# Supply.net
KiCad netlist of a schematic drawn in Altium Designer
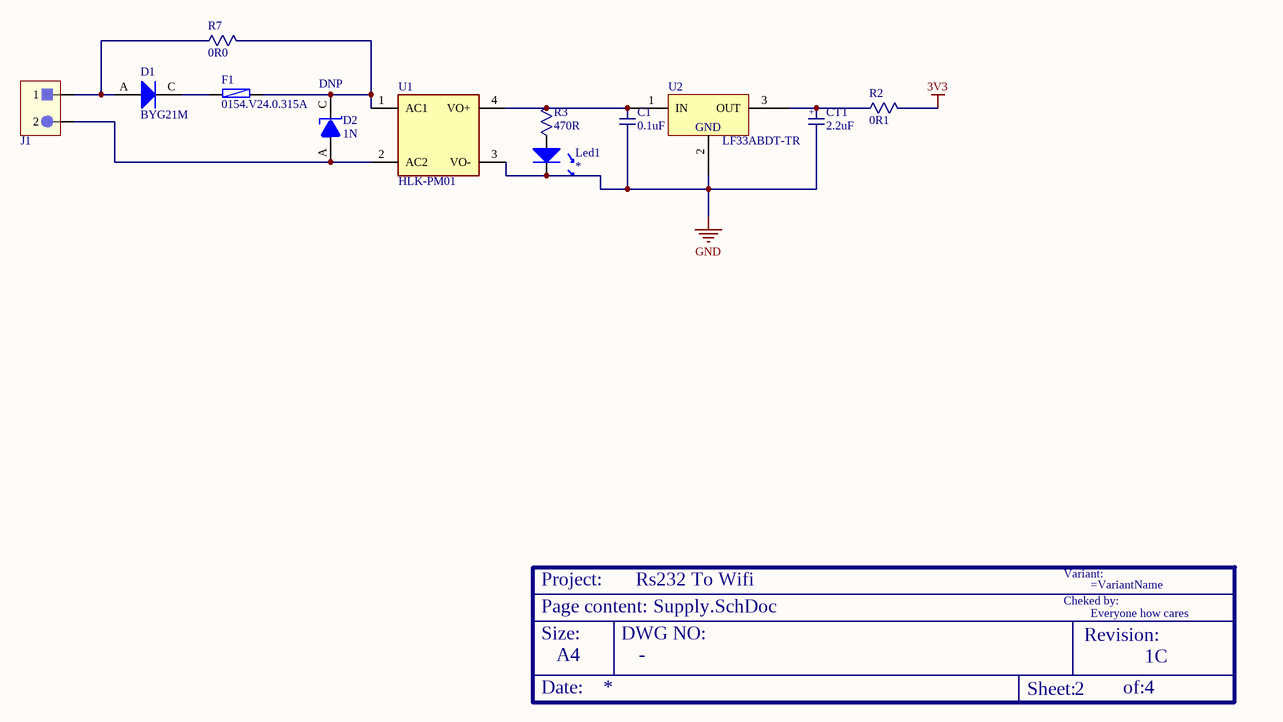
[diagram p0: Supply.SchDoc]

(export (version "E")
  (design (tool "Eeschema 10.0.6"))
  (components
    (comp (ref "C1")
      (value "0.1uF")
      (footprint "0603C")
      (description "Ceramic Capacitor")
      (libsource (lib "General_Libs") (part "CC"))
    )
    (comp (ref "CT1")
      (value "2.2uF")
      (footprint "1206T")
      (description "Condensador Tantalum")
      (fields (field (name "Comment") "Tantalum capacitor"))
      (libsource (lib "General_Libs") (part "CT"))
    )
    (comp (ref "D1")
      (value "BYG21M")
      (footprint "DO-214AC")
      (description "Diode")
      (fields (field (name "Comment") "DNP"))
      (libsource (lib "General_Libs") (part "Diode"))
    )
    (comp (ref "D2")
      (value "DNP")
      (footprint "1N5359BG")
      (description "Zener Diode")
      (fields (field (name "ALTIUM_VALUE") "1N"))
      (libsource (lib "General_Libs") (part "Zener Diode"))
    )
    (comp (ref "F1")
      (value "0154.V24.0.315A")
      (footprint "Fuseholder154")
      (description "Fusivel SMD LITTELFUSE  0154")
      (fields (field (name "Comment") "DNP"))
      (libsource (lib "General_Libs") (part "Fusivel_LITTELFUSE_0154"))
    )
    (comp (ref "J1")
      (value "Conector")
      (footprint "691313510002")
      (description "Conector 2 pins")
      (libsource (lib "General_Libs") (part "Conector 2 pins"))
    )
    (comp (ref "Led1")
      (value "Led")
      (footprint "LED_5MM_RED_1C-2A")
      (fields (field (name "ALTIUM_VALUE") "*"))
      (libsource (lib "General_Libs") (part "Led"))
    )
    (comp (ref "R2")
      (value "0R1")
      (footprint "0603")
      (description "Res")
      (libsource (lib "General_Libs") (part "Res"))
    )
    (comp (ref "R3")
      (value "470R")
      (footprint "0603")
      (description "Res")
      (libsource (lib "General_Libs") (part "Res"))
    )
    (comp (ref "R7")
      (value "0R0")
      (footprint "0805")
      (description "Res")
      (libsource (lib "General_Libs") (part "Res"))
    )
    (comp (ref "U1")
      (value "HLK-PM01")
      (footprint "HLK-PM01/ISE")
      (fields (field (name "MF") "Hi-link") (field (name "MP") "hlk-pm01"))
      (libsource (lib "General_Libs") (part "HLK-PM01"))
    )
    (comp (ref "U2")
      (value "LF33ABDT-TR")
      (footprint "DPAK-TO-252-3, CASE369C")
      (description "ST, LF33ABDT-TR, Fixed LDO Voltage Regulator, 3V to 16V, 400mV Dropout, 3.3Vout, 0.5Aout, TO-252-3")
      (fields (field (name "MANUFACTURER") "STMICROELECTRONICS") (field (name "Comment") "LDO"))
      (libsource (lib "General_Libs") (part "LF33ABDT-TR"))
    )
  )
  (nets
    (net (code "1") (name "3V3") (class "Default")
      (node (ref "R2") (pin "2") (pinfunction "2_2") (pintype "passive"))
    )
    (net (code "2") (name "GND") (class "Default")
      (node (ref "C1") (pin "2") (pinfunction "2_2") (pintype "passive"))
      (node (ref "CT1") (pin "2") (pinfunction "2_2") (pintype "passive"))
      (node (ref "Led1") (pin "C") (pinfunction "C_C") (pintype "passive"))
      (node (ref "U1") (pin "3") (pinfunction "VO-_3") (pintype "power_in"))
      (node (ref "U2") (pin "2") (pinfunction "GND_2") (pintype "passive"))
    )
    (net (code "3") (name "Net-(D1-PadA)") (class "Default")
      (node (ref "D1") (pin "A") (pinfunction "A_A") (pintype "passive"))
      (node (ref "J1") (pin "1") (pinfunction "1_1") (pintype "passive"))
      (node (ref "R7") (pin "1") (pinfunction "1_1") (pintype "passive"))
    )
    (net (code "4") (name "Net-(D1-PadC)") (class "Default")
      (node (ref "D1") (pin "C") (pinfunction "C_C") (pintype "passive"))
      (node (ref "F1") (pin "1") (pinfunction "1_1") (pintype "passive"))
    )
    (net (code "5") (name "Net-(Led1-PadA)") (class "Default")
      (node (ref "Led1") (pin "A") (pinfunction "A_A") (pintype "passive"))
      (node (ref "R3") (pin "1") (pinfunction "1_1") (pintype "passive"))
    )
    (net (code "6") (name "Net-(U1-AC1)") (class "Default")
      (node (ref "D2") (pin "C") (pinfunction "C_C") (pintype "passive"))
      (node (ref "F1") (pin "2") (pinfunction "2_2") (pintype "passive"))
      (node (ref "R7") (pin "2") (pinfunction "2_2") (pintype "passive"))
      (node (ref "U1") (pin "1") (pinfunction "AC1_1") (pintype "passive"))
    )
    (net (code "7") (name "Net-(U1-AC2)") (class "Default")
      (node (ref "D2") (pin "A") (pinfunction "A_A") (pintype "passive"))
      (node (ref "J1") (pin "2") (pinfunction "2_2") (pintype "passive"))
      (node (ref "U1") (pin "2") (pinfunction "AC2_2") (pintype "passive"))
    )
    (net (code "8") (name "Net-(U1-VO+)") (class "Default")
      (node (ref "C1") (pin "1") (pinfunction "1_1") (pintype "passive"))
      (node (ref "R3") (pin "2") (pinfunction "2_2") (pintype "passive"))
      (node (ref "U1") (pin "4") (pinfunction "VO+_4") (pintype "power_in"))
      (node (ref "U2") (pin "1") (pinfunction "IN_1") (pintype "passive"))
    )
    (net (code "9") (name "Net-(U2-OUT)") (class "Default")
      (node (ref "CT1") (pin "1") (pinfunction "1_1") (pintype "passive"))
      (node (ref "R2") (pin "1") (pinfunction "1_1") (pintype "passive"))
      (node (ref "U2") (pin "3") (pinfunction "OUT_3") (pintype "passive"))
    )
  )
)
